# caretaker-switch8.net
KiCad netlist of a schematic drawn in EAGLE
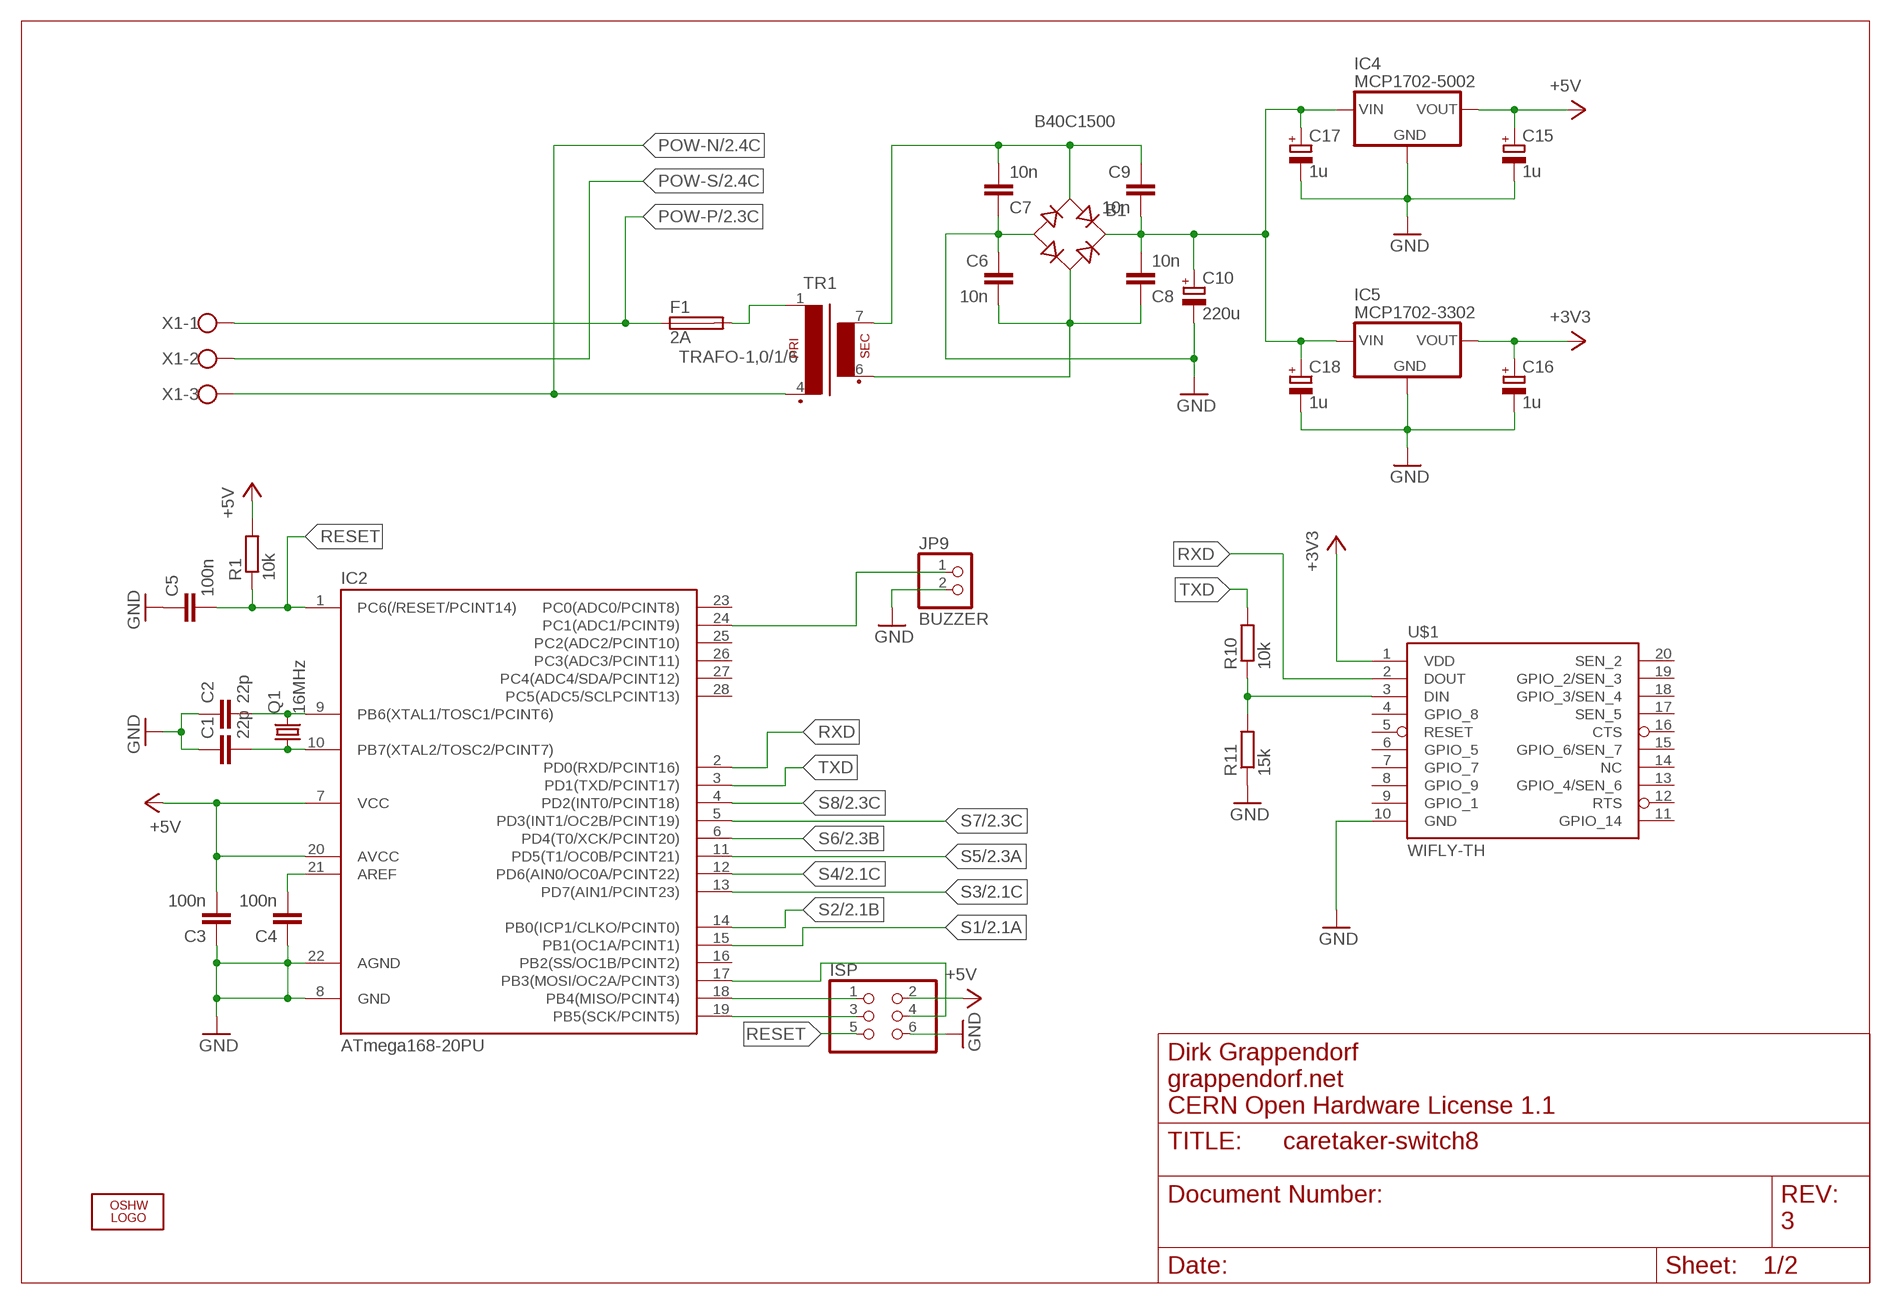
[diagram p0: schematic, sheet 1]
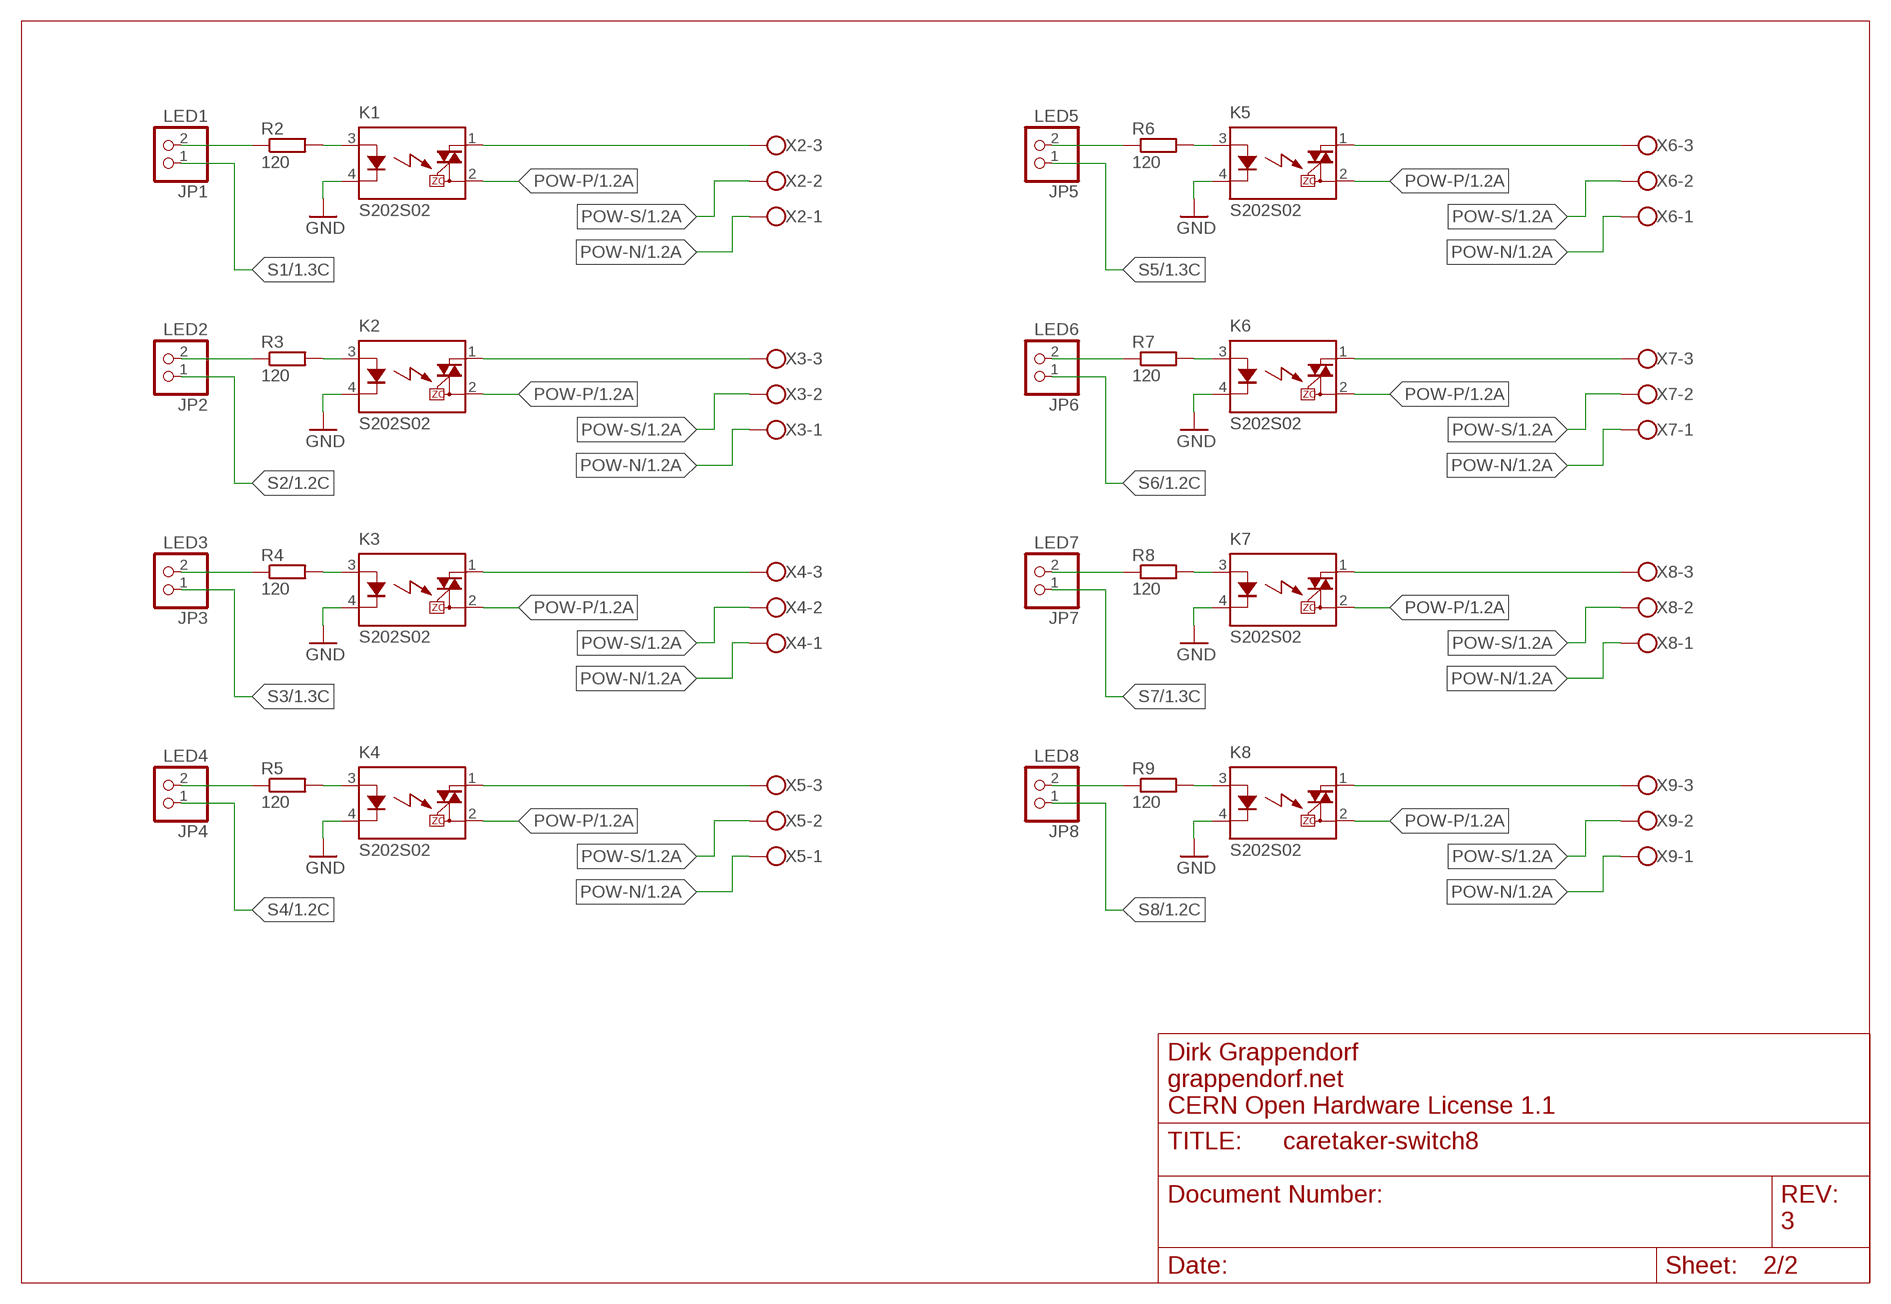
[diagram p1: schematic, sheet 2]

(export (version "E")
  (design (tool "Eeschema 10.0.6"))
  (components
    (comp (ref "JP1")
      (value "LED1")
      (footprint "eagle-import:1X02")
      (libsource (lib "eagle-import") (part "PINHD-1X2"))
    )
    (comp (ref "JP2")
      (value "LED2")
      (footprint "eagle-import:1X02")
      (libsource (lib "eagle-import") (part "PINHD-1X2"))
    )
    (comp (ref "JP3")
      (value "LED3")
      (footprint "eagle-import:1X02")
      (libsource (lib "eagle-import") (part "PINHD-1X2"))
    )
    (comp (ref "JP4")
      (value "LED4")
      (footprint "eagle-import:1X02")
      (libsource (lib "eagle-import") (part "PINHD-1X2"))
    )
    (comp (ref "JP5")
      (value "LED5")
      (footprint "eagle-import:1X02")
      (libsource (lib "eagle-import") (part "PINHD-1X2"))
    )
    (comp (ref "JP6")
      (value "LED6")
      (footprint "eagle-import:1X02")
      (libsource (lib "eagle-import") (part "PINHD-1X2"))
    )
    (comp (ref "JP7")
      (value "LED7")
      (footprint "eagle-import:1X02")
      (libsource (lib "eagle-import") (part "PINHD-1X2"))
    )
    (comp (ref "JP8")
      (value "LED8")
      (footprint "eagle-import:1X02")
      (libsource (lib "eagle-import") (part "PINHD-1X2"))
    )
    (comp (ref "K1")
      (value "S202S02")
      (footprint "eagle-import:S202S02")
      (libsource (lib "eagle-import") (part "S02S022"))
    )
    (comp (ref "K2")
      (value "S202S02")
      (footprint "eagle-import:S202S02")
      (libsource (lib "eagle-import") (part "S02S022"))
    )
    (comp (ref "K3")
      (value "S202S02")
      (footprint "eagle-import:S202S02")
      (libsource (lib "eagle-import") (part "S02S022"))
    )
    (comp (ref "K4")
      (value "S202S02")
      (footprint "eagle-import:S202S02")
      (libsource (lib "eagle-import") (part "S02S022"))
    )
    (comp (ref "K5")
      (value "S202S02")
      (footprint "eagle-import:S202S02")
      (libsource (lib "eagle-import") (part "S02S022"))
    )
    (comp (ref "K6")
      (value "S202S02")
      (footprint "eagle-import:S202S02")
      (libsource (lib "eagle-import") (part "S02S022"))
    )
    (comp (ref "K7")
      (value "S202S02")
      (footprint "eagle-import:S202S02")
      (libsource (lib "eagle-import") (part "S02S022"))
    )
    (comp (ref "K8")
      (value "S202S02")
      (footprint "eagle-import:S202S02")
      (libsource (lib "eagle-import") (part "S02S022"))
    )
    (comp (ref "R2")
      (value "120")
      (footprint "eagle-import:0204_7")
      (libsource (lib "eagle-import") (part "R-EU_0204/7"))
    )
    (comp (ref "R3")
      (value "120")
      (footprint "eagle-import:0204_7")
      (libsource (lib "eagle-import") (part "R-EU_0204/7"))
    )
    (comp (ref "R4")
      (value "120")
      (footprint "eagle-import:0204_7")
      (libsource (lib "eagle-import") (part "R-EU_0204/7"))
    )
    (comp (ref "R5")
      (value "120")
      (footprint "eagle-import:0204_7")
      (libsource (lib "eagle-import") (part "R-EU_0204/7"))
    )
    (comp (ref "R6")
      (value "120")
      (footprint "eagle-import:0204_7")
      (libsource (lib "eagle-import") (part "R-EU_0204/7"))
    )
    (comp (ref "R7")
      (value "120")
      (footprint "eagle-import:0204_7")
      (libsource (lib "eagle-import") (part "R-EU_0204/7"))
    )
    (comp (ref "R8")
      (value "120")
      (footprint "eagle-import:0204_7")
      (libsource (lib "eagle-import") (part "R-EU_0204/7"))
    )
    (comp (ref "R9")
      (value "120")
      (footprint "eagle-import:0204_7")
      (libsource (lib "eagle-import") (part "R-EU_0204/7"))
    )
    (comp (ref "X2")
      (value "W237-103")
      (footprint "eagle-import:W237-103")
      (libsource (lib "eagle-import") (part "W237-103"))
    )
    (comp (ref "X3")
      (value "W237-103")
      (footprint "eagle-import:W237-103")
      (libsource (lib "eagle-import") (part "W237-103"))
    )
    (comp (ref "X4")
      (value "W237-103")
      (footprint "eagle-import:W237-103")
      (libsource (lib "eagle-import") (part "W237-103"))
    )
    (comp (ref "X5")
      (value "W237-103")
      (footprint "eagle-import:W237-103")
      (libsource (lib "eagle-import") (part "W237-103"))
    )
    (comp (ref "X6")
      (value "W237-103")
      (footprint "eagle-import:W237-103")
      (libsource (lib "eagle-import") (part "W237-103"))
    )
    (comp (ref "X7")
      (value "W237-103")
      (footprint "eagle-import:W237-103")
      (libsource (lib "eagle-import") (part "W237-103"))
    )
    (comp (ref "X8")
      (value "W237-103")
      (footprint "eagle-import:W237-103")
      (libsource (lib "eagle-import") (part "W237-103"))
    )
    (comp (ref "X9")
      (value "W237-103")
      (footprint "eagle-import:W237-103")
      (libsource (lib "eagle-import") (part "W237-103"))
    )
    (comp (ref "B1")
      (value "B40C1500")
      (footprint "eagle-import:2KBB")
      (libsource (lib "eagle-import") (part "RECTIFIER-2KBB"))
    )
    (comp (ref "C1")
      (value "22p")
      (footprint "eagle-import:C025-025X050")
      (libsource (lib "eagle-import") (part "C-EU025-025X050"))
    )
    (comp (ref "C2")
      (value "22p")
      (footprint "eagle-import:C025-025X050")
      (libsource (lib "eagle-import") (part "C-EU025-025X050"))
    )
    (comp (ref "C3")
      (value "100n")
      (footprint "eagle-import:C025-024X044")
      (libsource (lib "eagle-import") (part "C-EU025-024X044"))
    )
    (comp (ref "C4")
      (value "100n")
      (footprint "eagle-import:C025-024X044")
      (libsource (lib "eagle-import") (part "C-EU025-024X044"))
    )
    (comp (ref "C5")
      (value "100n")
      (footprint "eagle-import:C025-024X044")
      (libsource (lib "eagle-import") (part "C-EU025-024X044"))
    )
    (comp (ref "C6")
      (value "10n")
      (footprint "eagle-import:C025-024X044")
      (libsource (lib "eagle-import") (part "C-EU025-024X044"))
    )
    (comp (ref "C7")
      (value "10n")
      (footprint "eagle-import:C025-024X044")
      (libsource (lib "eagle-import") (part "C-EU025-024X044"))
    )
    (comp (ref "C8")
      (value "10n")
      (footprint "eagle-import:C025-024X044")
      (libsource (lib "eagle-import") (part "C-EU025-024X044"))
    )
    (comp (ref "C9")
      (value "10n")
      (footprint "eagle-import:C025-024X044")
      (libsource (lib "eagle-import") (part "C-EU025-024X044"))
    )
    (comp (ref "C10")
      (value "220u")
      (footprint "eagle-import:E3,5-8")
      (libsource (lib "eagle-import") (part "CPOL-EUE3.5-8"))
    )
    (comp (ref "C15")
      (value "1u")
      (footprint "eagle-import:E2,5-5")
      (libsource (lib "eagle-import") (part "CPOL-EUE2.5-5"))
    )
    (comp (ref "C16")
      (value "1u")
      (footprint "eagle-import:E2,5-5")
      (libsource (lib "eagle-import") (part "CPOL-EUE2.5-5"))
    )
    (comp (ref "C17")
      (value "1u")
      (footprint "eagle-import:E2,5-5")
      (libsource (lib "eagle-import") (part "CPOL-EUE2.5-5"))
    )
    (comp (ref "C18")
      (value "1u")
      (footprint "eagle-import:E2,5-5")
      (libsource (lib "eagle-import") (part "CPOL-EUE2.5-5"))
    )
    (comp (ref "F1")
      (value "2A")
      (footprint "eagle-import:SH22,5")
      (libsource (lib "eagle-import") (part "SH22,5"))
    )
    (comp (ref "IC2")
      (value "ATmega168-20PU")
      (footprint "eagle-import:DIL28-3")
      (libsource (lib "eagle-import") (part "ATMEGA48/88/168-PU"))
    )
    (comp (ref "IC4")
      (value "MCP1702-5002")
      (footprint "eagle-import:MCP1702")
      (libsource (lib "eagle-import") (part "MCP1702"))
    )
    (comp (ref "IC5")
      (value "MCP1702-3302")
      (footprint "eagle-import:MCP1702")
      (libsource (lib "eagle-import") (part "MCP1702"))
    )
    (comp (ref "ISP")
      (value "PINHD-2X3")
      (footprint "eagle-import:2X03")
      (libsource (lib "eagle-import") (part "PINHD-2X3"))
    )
    (comp (ref "JP9")
      (value "BUZZER")
      (footprint "eagle-import:1X02")
      (libsource (lib "eagle-import") (part "PINHD-1X2"))
    )
    (comp (ref "LOGO1")
      (value "OSHW_LOGO_10MILX0350-NT-BOTTOM")
      (footprint "eagle-import:OSHW_10X350_NOTEXT_BOTTOM")
      (libsource (lib "eagle-import") (part "OSHW_LOGO_10MILX0350-NT-BOTTOM"))
    )
    (comp (ref "Q1")
      (value "16MHz")
      (footprint "eagle-import:HC49U-V")
      (libsource (lib "eagle-import") (part "CRYSTALHC49U-V"))
    )
    (comp (ref "R1")
      (value "10k")
      (footprint "eagle-import:0204_7")
      (libsource (lib "eagle-import") (part "R-EU_0204/7"))
    )
    (comp (ref "R10")
      (value "10k")
      (footprint "eagle-import:0204_7")
      (libsource (lib "eagle-import") (part "R-EU_0204/7"))
    )
    (comp (ref "R11")
      (value "15k")
      (footprint "eagle-import:0204_7")
      (libsource (lib "eagle-import") (part "R-EU_0204/7"))
    )
    (comp (ref "TR1")
      (value "TRAFO-1,0/1/6")
      (footprint "eagle-import:TRAFO-1,0_1_6")
      (libsource (lib "eagle-import") (part "TRAFO-1,0/1/6"))
    )
    (comp (ref "U$1")
      (value "WIFLY-TH")
      (footprint "eagle-import:WIFLY-TH")
      (libsource (lib "eagle-import") (part "WIFLY-TH"))
    )
    (comp (ref "X1")
      (value "W237-103")
      (footprint "eagle-import:W237-103")
      (libsource (lib "eagle-import") (part "W237-103"))
    )
  )
  (nets
    (net (code "1") (name "+3V3") (class "Default")
      (node (ref "C16") (pin "+") (pinfunction "+_+") (pintype "passive"))
      (node (ref "IC5") (pin "VOUT") (pinfunction "OUT_VOUT") (pintype "passive"))
      (node (ref "U$1") (pin "1") (pinfunction "VDD_1") (pintype "power_in"))
    )
    (net (code "2") (name "+5V") (class "Default")
      (node (ref "C15") (pin "+") (pinfunction "+_+") (pintype "passive"))
      (node (ref "C3") (pin "2") (pinfunction "2_2") (pintype "passive"))
      (node (ref "IC2") (pin "20") (pinfunction "AVCC_20") (pintype "passive"))
      (node (ref "IC2") (pin "7") (pinfunction "VCC_7") (pintype "power_in"))
      (node (ref "IC4") (pin "VOUT") (pinfunction "OUT_VOUT") (pintype "passive"))
      (node (ref "ISP") (pin "2") (pinfunction "2_2") (pintype "passive"))
      (node (ref "R1") (pin "2") (pinfunction "2_2") (pintype "passive"))
    )
    (net (code "3") (name "GND") (class "Default")
      (node (ref "B1") (pin "-") (pinfunction "-_-") (pintype "passive"))
      (node (ref "C1") (pin "1") (pinfunction "1_1") (pintype "passive"))
      (node (ref "C10") (pin "-") (pinfunction "-_-") (pintype "passive"))
      (node (ref "C15") (pin "-") (pinfunction "-_-") (pintype "passive"))
      (node (ref "C16") (pin "-") (pinfunction "-_-") (pintype "passive"))
      (node (ref "C17") (pin "-") (pinfunction "-_-") (pintype "passive"))
      (node (ref "C18") (pin "-") (pinfunction "-_-") (pintype "passive"))
      (node (ref "C2") (pin "1") (pinfunction "1_1") (pintype "passive"))
      (node (ref "C3") (pin "1") (pinfunction "1_1") (pintype "passive"))
      (node (ref "C4") (pin "1") (pinfunction "1_1") (pintype "passive"))
      (node (ref "C5") (pin "1") (pinfunction "1_1") (pintype "passive"))
      (node (ref "C6") (pin "1") (pinfunction "1_1") (pintype "passive"))
      (node (ref "C7") (pin "1") (pinfunction "1_1") (pintype "passive"))
      (node (ref "IC2") (pin "22") (pinfunction "AGND_22") (pintype "power_in"))
      (node (ref "IC2") (pin "8") (pinfunction "GND_8") (pintype "power_in"))
      (node (ref "IC4") (pin "GND") (pinfunction "GND_GND") (pintype "input"))
      (node (ref "IC5") (pin "GND") (pinfunction "GND_GND") (pintype "input"))
      (node (ref "ISP") (pin "6") (pinfunction "6_6") (pintype "passive"))
      (node (ref "JP9") (pin "2") (pinfunction "2_2") (pintype "passive"))
      (node (ref "K1") (pin "4") (pinfunction "K_4") (pintype "passive"))
      (node (ref "K2") (pin "4") (pinfunction "K_4") (pintype "passive"))
      (node (ref "K3") (pin "4") (pinfunction "K_4") (pintype "passive"))
      (node (ref "K4") (pin "4") (pinfunction "K_4") (pintype "passive"))
      (node (ref "K5") (pin "4") (pinfunction "K_4") (pintype "passive"))
      (node (ref "K6") (pin "4") (pinfunction "K_4") (pintype "passive"))
      (node (ref "K7") (pin "4") (pinfunction "K_4") (pintype "passive"))
      (node (ref "K8") (pin "4") (pinfunction "K_4") (pintype "passive"))
      (node (ref "R11") (pin "1") (pinfunction "1_1") (pintype "passive"))
      (node (ref "U$1") (pin "10") (pinfunction "GND_10") (pintype "power_in"))
    )
    (net (code "4") (name "Net-(IC2-AREF)") (class "Default")
      (node (ref "C4") (pin "2") (pinfunction "2_2") (pintype "passive"))
      (node (ref "IC2") (pin "21") (pinfunction "AREF_21") (pintype "passive"))
    )
    (net (code "5") (name "Net-(IC2-PB3(MOSI{slash}OC2A{slash}PCINT3))") (class "Default")
      (node (ref "IC2") (pin "17") (pinfunction "PB3(MOSI/OC2A/PCINT3)_17") (pintype "bidirectional"))
      (node (ref "ISP") (pin "4") (pinfunction "4_4") (pintype "passive"))
    )
    (net (code "6") (name "Net-(IC2-PB4(MISO{slash}PCINT4))") (class "Default")
      (node (ref "IC2") (pin "18") (pinfunction "PB4(MISO/PCINT4)_18") (pintype "bidirectional"))
      (node (ref "ISP") (pin "1") (pinfunction "1_1") (pintype "passive"))
    )
    (net (code "7") (name "Net-(IC2-PB5(SCK{slash}PCINT5))") (class "Default")
      (node (ref "IC2") (pin "19") (pinfunction "PB5(SCK/PCINT5)_19") (pintype "bidirectional"))
      (node (ref "ISP") (pin "3") (pinfunction "3_3") (pintype "passive"))
    )
    (net (code "8") (name "Net-(IC2-PB6(XTAL1{slash}TOSC1{slash}PCINT6))") (class "Default")
      (node (ref "C2") (pin "2") (pinfunction "2_2") (pintype "passive"))
      (node (ref "IC2") (pin "9") (pinfunction "PB6(XTAL1/TOSC1/PCINT6)_9") (pintype "bidirectional"))
      (node (ref "Q1") (pin "2") (pinfunction "2_2") (pintype "passive"))
    )
    (net (code "9") (name "Net-(IC2-PB7(XTAL2{slash}TOSC2{slash}PCINT7))") (class "Default")
      (node (ref "C1") (pin "2") (pinfunction "2_2") (pintype "passive"))
      (node (ref "IC2") (pin "10") (pinfunction "PB7(XTAL2/TOSC2/PCINT7)_10") (pintype "bidirectional"))
      (node (ref "Q1") (pin "1") (pinfunction "1_1") (pintype "passive"))
    )
    (net (code "10") (name "Net-(IC2-PC1(ADC1{slash}PCINT9))") (class "Default")
      (node (ref "IC2") (pin "24") (pinfunction "PC1(ADC1/PCINT9)_24") (pintype "bidirectional"))
      (node (ref "JP9") (pin "1") (pinfunction "1_1") (pintype "passive"))
    )
    (net (code "11") (name "Net-(IC4-IN)") (class "Default")
      (node (ref "B1") (pin "+") (pinfunction "+_+") (pintype "passive"))
      (node (ref "C10") (pin "+") (pinfunction "+_+") (pintype "passive"))
      (node (ref "C17") (pin "+") (pinfunction "+_+") (pintype "passive"))
      (node (ref "C18") (pin "+") (pinfunction "+_+") (pintype "passive"))
      (node (ref "C8") (pin "2") (pinfunction "2_2") (pintype "passive"))
      (node (ref "C9") (pin "2") (pinfunction "2_2") (pintype "passive"))
      (node (ref "IC4") (pin "VIN") (pinfunction "IN_VIN") (pintype "input"))
      (node (ref "IC5") (pin "VIN") (pinfunction "IN_VIN") (pintype "input"))
    )
    (net (code "12") (name "Net-(JP1-Pad2)") (class "Default")
      (node (ref "JP1") (pin "2") (pinfunction "2_2") (pintype "passive"))
      (node (ref "R2") (pin "1") (pinfunction "1_1") (pintype "passive"))
    )
    (net (code "13") (name "Net-(JP2-Pad2)") (class "Default")
      (node (ref "JP2") (pin "2") (pinfunction "2_2") (pintype "passive"))
      (node (ref "R3") (pin "1") (pinfunction "1_1") (pintype "passive"))
    )
    (net (code "14") (name "Net-(JP3-Pad2)") (class "Default")
      (node (ref "JP3") (pin "2") (pinfunction "2_2") (pintype "passive"))
      (node (ref "R4") (pin "1") (pinfunction "1_1") (pintype "passive"))
    )
    (net (code "15") (name "Net-(JP4-Pad2)") (class "Default")
      (node (ref "JP4") (pin "2") (pinfunction "2_2") (pintype "passive"))
      (node (ref "R5") (pin "1") (pinfunction "1_1") (pintype "passive"))
    )
    (net (code "16") (name "Net-(JP5-Pad2)") (class "Default")
      (node (ref "JP5") (pin "2") (pinfunction "2_2") (pintype "passive"))
      (node (ref "R6") (pin "1") (pinfunction "1_1") (pintype "passive"))
    )
    (net (code "17") (name "Net-(JP6-Pad2)") (class "Default")
      (node (ref "JP6") (pin "2") (pinfunction "2_2") (pintype "passive"))
      (node (ref "R7") (pin "1") (pinfunction "1_1") (pintype "passive"))
    )
    (net (code "18") (name "Net-(JP7-Pad2)") (class "Default")
      (node (ref "JP7") (pin "2") (pinfunction "2_2") (pintype "passive"))
      (node (ref "R8") (pin "1") (pinfunction "1_1") (pintype "passive"))
    )
    (net (code "19") (name "Net-(JP8-Pad2)") (class "Default")
      (node (ref "JP8") (pin "2") (pinfunction "2_2") (pintype "passive"))
      (node (ref "R9") (pin "1") (pinfunction "1_1") (pintype "passive"))
    )
    (net (code "20") (name "Net-(K1-A)") (class "Default")
      (node (ref "K1") (pin "3") (pinfunction "A_3") (pintype "passive"))
      (node (ref "R2") (pin "2") (pinfunction "2_2") (pintype "passive"))
    )
    (net (code "21") (name "Net-(K1-DS1)") (class "Default")
      (node (ref "K1") (pin "1") (pinfunction "DS1_1") (pintype "passive"))
      (node (ref "X2") (pin "3") (pinfunction "KL_3") (pintype "passive"))
    )
    (net (code "22") (name "Net-(K2-A)") (class "Default")
      (node (ref "K2") (pin "3") (pinfunction "A_3") (pintype "passive"))
      (node (ref "R3") (pin "2") (pinfunction "2_2") (pintype "passive"))
    )
    (net (code "23") (name "Net-(K2-DS1)") (class "Default")
      (node (ref "K2") (pin "1") (pinfunction "DS1_1") (pintype "passive"))
      (node (ref "X3") (pin "3") (pinfunction "KL_3") (pintype "passive"))
    )
    (net (code "24") (name "Net-(K3-A)") (class "Default")
      (node (ref "K3") (pin "3") (pinfunction "A_3") (pintype "passive"))
      (node (ref "R4") (pin "2") (pinfunction "2_2") (pintype "passive"))
    )
    (net (code "25") (name "Net-(K3-DS1)") (class "Default")
      (node (ref "K3") (pin "1") (pinfunction "DS1_1") (pintype "passive"))
      (node (ref "X4") (pin "3") (pinfunction "KL_3") (pintype "passive"))
    )
    (net (code "26") (name "Net-(K4-A)") (class "Default")
      (node (ref "K4") (pin "3") (pinfunction "A_3") (pintype "passive"))
      (node (ref "R5") (pin "2") (pinfunction "2_2") (pintype "passive"))
    )
    (net (code "27") (name "Net-(K4-DS1)") (class "Default")
      (node (ref "K4") (pin "1") (pinfunction "DS1_1") (pintype "passive"))
      (node (ref "X5") (pin "3") (pinfunction "KL_3") (pintype "passive"))
    )
    (net (code "28") (name "Net-(K5-A)") (class "Default")
      (node (ref "K5") (pin "3") (pinfunction "A_3") (pintype "passive"))
      (node (ref "R6") (pin "2") (pinfunction "2_2") (pintype "passive"))
    )
    (net (code "29") (name "Net-(K5-DS1)") (class "Default")
      (node (ref "K5") (pin "1") (pinfunction "DS1_1") (pintype "passive"))
      (node (ref "X6") (pin "3") (pinfunction "KL_3") (pintype "passive"))
    )
    (net (code "30") (name "Net-(K6-A)") (class "Default")
      (node (ref "K6") (pin "3") (pinfunction "A_3") (pintype "passive"))
      (node (ref "R7") (pin "2") (pinfunction "2_2") (pintype "passive"))
    )
    (net (code "31") (name "Net-(K6-DS1)") (class "Default")
      (node (ref "K6") (pin "1") (pinfunction "DS1_1") (pintype "passive"))
      (node (ref "X7") (pin "3") (pinfunction "KL_3") (pintype "passive"))
    )
    (net (code "32") (name "Net-(K7-A)") (class "Default")
      (node (ref "K7") (pin "3") (pinfunction "A_3") (pintype "passive"))
      (node (ref "R8") (pin "2") (pinfunction "2_2") (pintype "passive"))
    )
    (net (code "33") (name "Net-(K7-DS1)") (class "Default")
      (node (ref "K7") (pin "1") (pinfunction "DS1_1") (pintype "passive"))
      (node (ref "X8") (pin "3") (pinfunction "KL_3") (pintype "passive"))
    )
    (net (code "34") (name "Net-(K8-A)") (class "Default")
      (node (ref "K8") (pin "3") (pinfunction "A_3") (pintype "passive"))
      (node (ref "R9") (pin "2") (pinfunction "2_2") (pintype "passive"))
    )
    (net (code "35") (name "Net-(K8-DS1)") (class "Default")
      (node (ref "K8") (pin "1") (pinfunction "DS1_1") (pintype "passive"))
      (node (ref "X9") (pin "3") (pinfunction "KL_3") (pintype "passive"))
    )
    (net (code "36") (name "Net-(TR1-P1)") (class "Default")
      (node (ref "F1") (pin "2") (pinfunction "2_2") (pintype "passive"))
      (node (ref "TR1") (pin "1") (pinfunction "P1_1") (pintype "passive"))
    )
    (net (code "37") (name "Net-(TR1-S3)") (class "Default")
      (node (ref "B1") (pin "AC2") (pinfunction "AC2_AC2") (pintype "passive"))
      (node (ref "C6") (pin "2") (pinfunction "2_2") (pintype "passive"))
      (node (ref "C8") (pin "1") (pinfunction "1_1") (pintype "passive"))
      (node (ref "TR1") (pin "6") (pinfunction "S3_6") (pintype "passive"))
    )
    (net (code "38") (name "Net-(TR1-S4)") (class "Default")
      (node (ref "B1") (pin "AC1") (pinfunction "AC1_AC1") (pintype "passive"))
      (node (ref "C7") (pin "2") (pinfunction "2_2") (pintype "passive"))
      (node (ref "C9") (pin "1") (pinfunction "1_1") (pintype "passive"))
      (node (ref "TR1") (pin "7") (pinfunction "S4_7") (pintype "passive"))
    )
    (net (code "39") (name "Net-(U$1-DIN)") (class "Default")
      (node (ref "R10") (pin "1") (pinfunction "1_1") (pintype "passive"))
      (node (ref "R11") (pin "2") (pinfunction "2_2") (pintype "passive"))
      (node (ref "U$1") (pin "3") (pinfunction "DIN_3") (pintype "input"))
    )
    (net (code "40") (name "POW-N") (class "Default")
      (node (ref "TR1") (pin "4") (pinfunction "P2_4") (pintype "passive"))
      (node (ref "X1") (pin "3") (pinfunction "KL_3") (pintype "passive"))
      (node (ref "X2") (pin "1") (pinfunction "KL_1") (pintype "passive"))
      (node (ref "X3") (pin "1") (pinfunction "KL_1") (pintype "passive"))
      (node (ref "X4") (pin "1") (pinfunction "KL_1") (pintype "passive"))
      (node (ref "X5") (pin "1") (pinfunction "KL_1") (pintype "passive"))
      (node (ref "X6") (pin "1") (pinfunction "KL_1") (pintype "passive"))
      (node (ref "X7") (pin "1") (pinfunction "KL_1") (pintype "passive"))
      (node (ref "X8") (pin "1") (pinfunction "KL_1") (pintype "passive"))
      (node (ref "X9") (pin "1") (pinfunction "KL_1") (pintype "passive"))
    )
    (net (code "41") (name "POW-P") (class "Default")
      (node (ref "F1") (pin "1") (pinfunction "1_1") (pintype "passive"))
      (node (ref "K1") (pin "2") (pinfunction "DS2_2") (pintype "passive"))
      (node (ref "K2") (pin "2") (pinfunction "DS2_2") (pintype "passive"))
      (node (ref "K3") (pin "2") (pinfunction "DS2_2") (pintype "passive"))
      (node (ref "K4") (pin "2") (pinfunction "DS2_2") (pintype "passive"))
      (node (ref "K5") (pin "2") (pinfunction "DS2_2") (pintype "passive"))
      (node (ref "K6") (pin "2") (pinfunction "DS2_2") (pintype "passive"))
      (node (ref "K7") (pin "2") (pinfunction "DS2_2") (pintype "passive"))
      (node (ref "K8") (pin "2") (pinfunction "DS2_2") (pintype "passive"))
      (node (ref "X1") (pin "1") (pinfunction "KL_1") (pintype "passive"))
    )
    (net (code "42") (name "POW-S") (class "Default")
      (node (ref "X1") (pin "2") (pinfunction "KL_2") (pintype "passive"))
      (node (ref "X2") (pin "2") (pinfunction "KL_2") (pintype "passive"))
      (node (ref "X3") (pin "2") (pinfunction "KL_2") (pintype "passive"))
      (node (ref "X4") (pin "2") (pinfunction "KL_2") (pintype "passive"))
      (node (ref "X5") (pin "2") (pinfunction "KL_2") (pintype "passive"))
      (node (ref "X6") (pin "2") (pinfunction "KL_2") (pintype "passive"))
      (node (ref "X7") (pin "2") (pinfunction "KL_2") (pintype "passive"))
      (node (ref "X8") (pin "2") (pinfunction "KL_2") (pintype "passive"))
      (node (ref "X9") (pin "2") (pinfunction "KL_2") (pintype "passive"))
    )
    (net (code "43") (name "RESET") (class "Default")
      (node (ref "C5") (pin "2") (pinfunction "2_2") (pintype "passive"))
      (node (ref "IC2") (pin "1") (pinfunction "PC6(/RESET/PCINT14)_1") (pintype "bidirectional"))
      (node (ref "ISP") (pin "5") (pinfunction "5_5") (pintype "passive"))
      (node (ref "R1") (pin "1") (pinfunction "1_1") (pintype "passive"))
    )
    (net (code "44") (name "RXD") (class "Default")
      (node (ref "IC2") (pin "2") (pinfunction "PD0(RXD/PCINT16)_2") (pintype "bidirectional"))
      (node (ref "U$1") (pin "2") (pinfunction "DOUT_2") (pintype "output"))
    )
    (net (code "45") (name "S1") (class "Default")
      (node (ref "IC2") (pin "15") (pinfunction "PB1(OC1A/PCINT1)_15") (pintype "bidirectional"))
      (node (ref "JP1") (pin "1") (pinfunction "1_1") (pintype "passive"))
    )
    (net (code "46") (name "S2") (class "Default")
      (node (ref "IC2") (pin "14") (pinfunction "PB0(ICP1/CLKO/PCINT0)_14") (pintype "bidirectional"))
      (node (ref "JP2") (pin "1") (pinfunction "1_1") (pintype "passive"))
    )
    (net (code "47") (name "S3") (class "Default")
      (node (ref "IC2") (pin "13") (pinfunction "PD7(AIN1/PCINT23)_13") (pintype "bidirectional"))
      (node (ref "JP3") (pin "1") (pinfunction "1_1") (pintype "passive"))
    )
    (net (code "48") (name "S4") (class "Default")
      (node (ref "IC2") (pin "12") (pinfunction "PD6(AIN0/OC0A/PCINT22)_12") (pintype "bidirectional"))
      (node (ref "JP4") (pin "1") (pinfunction "1_1") (pintype "passive"))
    )
    (net (code "49") (name "S5") (class "Default")
      (node (ref "IC2") (pin "11") (pinfunction "PD5(T1/OC0B/PCINT21)_11") (pintype "bidirectional"))
      (node (ref "JP5") (pin "1") (pinfunction "1_1") (pintype "passive"))
    )
    (net (code "50") (name "S6") (class "Default")
      (node (ref "IC2") (pin "6") (pinfunction "PD4(T0/XCK/PCINT20)_6") (pintype "bidirectional"))
      (node (ref "JP6") (pin "1") (pinfunction "1_1") (pintype "passive"))
    )
    (net (code "51") (name "S7") (class "Default")
      (node (ref "IC2") (pin "5") (pinfunction "PD3(INT1/OC2B/PCINT19)_5") (pintype "bidirectional"))
      (node (ref "JP7") (pin "1") (pinfunction "1_1") (pintype "passive"))
    )
    (net (code "52") (name "S8") (class "Default")
      (node (ref "IC2") (pin "4") (pinfunction "PD2(INT0/PCINT18)_4") (pintype "bidirectional"))
      (node (ref "JP8") (pin "1") (pinfunction "1_1") (pintype "passive"))
    )
    (net (code "53") (name "TXD") (class "Default")
      (node (ref "IC2") (pin "3") (pinfunction "PD1(TXD/PCINT17)_3") (pintype "bidirectional"))
      (node (ref "R10") (pin "2") (pinfunction "2_2") (pintype "passive"))
    )
    (net (code "54") (name "unconnected-(IC2-PB2(SS{slash}OC1B{slash}PCINT2)-Pad16)") (class "Default")
      (node (ref "IC2") (pin "16") (pinfunction "PB2(SS/OC1B/PCINT2)_16") (pintype "bidirectional"))
    )
    (net (code "55") (name "unconnected-(IC2-PC0(ADC0{slash}PCINT8)-Pad23)") (class "Default")
      (node (ref "IC2") (pin "23") (pinfunction "PC0(ADC0/PCINT8)_23") (pintype "bidirectional"))
    )
    (net (code "56") (name "unconnected-(IC2-PC2(ADC2{slash}PCINT10)-Pad25)") (class "Default")
      (node (ref "IC2") (pin "25") (pinfunction "PC2(ADC2/PCINT10)_25") (pintype "bidirectional"))
    )
    (net (code "57") (name "unconnected-(IC2-PC3(ADC3{slash}PCINT11)-Pad26)") (class "Default")
      (node (ref "IC2") (pin "26") (pinfunction "PC3(ADC3/PCINT11)_26") (pintype "bidirectional"))
    )
    (net (code "58") (name "unconnected-(IC2-PC4(ADC4{slash}SDA{slash}PCINT12)-Pad27)") (class "Default")
      (node (ref "IC2") (pin "27") (pinfunction "PC4(ADC4/SDA/PCINT12)_27") (pintype "bidirectional"))
    )
    (net (code "59") (name "unconnected-(IC2-PC5(ADC5{slash}SCLPCINT13)-Pad28)") (class "Default")
      (node (ref "IC2") (pin "28") (pinfunction "PC5(ADC5/SCLPCINT13)_28") (pintype "bidirectional"))
    )
    (net (code "60") (name "unconnected-(U$1-CTS-Pad16)") (class "Default")
      (node (ref "U$1") (pin "16") (pinfunction "CTS_16") (pintype "input"))
    )
    (net (code "61") (name "unconnected-(U$1-GPIO_1-Pad9)") (class "Default")
      (node (ref "U$1") (pin "9") (pinfunction "GPIO_1_9") (pintype "bidirectional"))
    )
    (net (code "62") (name "unconnected-(U$1-GPIO_2{slash}SEN_3-Pad19)") (class "Default")
      (node (ref "U$1") (pin "19") (pinfunction "GPIO_2/SEN_3_19") (pintype "bidirectional"))
    )
    (net (code "63") (name "unconnected-(U$1-GPIO_3{slash}SEN_4-Pad18)") (class "Default")
      (node (ref "U$1") (pin "18") (pinfunction "GPIO_3/SEN_4_18") (pintype "bidirectional"))
    )
    (net (code "64") (name "unconnected-(U$1-GPIO_4{slash}SEN_6-Pad13)") (class "Default")
      (node (ref "U$1") (pin "13") (pinfunction "GPIO_4/SEN_6_13") (pintype "bidirectional"))
    )
    (net (code "65") (name "unconnected-(U$1-GPIO_5-Pad6)") (class "Default")
      (node (ref "U$1") (pin "6") (pinfunction "GPIO_5_6") (pintype "bidirectional"))
    )
    (net (code "66") (name "unconnected-(U$1-GPIO_6{slash}SEN_7-Pad15)") (class "Default")
      (node (ref "U$1") (pin "15") (pinfunction "GPIO_6/SEN_7_15") (pintype "bidirectional"))
    )
    (net (code "67") (name "unconnected-(U$1-GPIO_7-Pad7)") (class "Default")
      (node (ref "U$1") (pin "7") (pinfunction "GPIO_7_7") (pintype "bidirectional"))
    )
    (net (code "68") (name "unconnected-(U$1-GPIO_8-Pad4)") (class "Default")
      (node (ref "U$1") (pin "4") (pinfunction "GPIO_8_4") (pintype "bidirectional"))
    )
    (net (code "69") (name "unconnected-(U$1-GPIO_9-Pad8)") (class "Default")
      (node (ref "U$1") (pin "8") (pinfunction "GPIO_9_8") (pintype "bidirectional"))
    )
    (net (code "70") (name "unconnected-(U$1-GPIO_14-Pad11)") (class "Default")
      (node (ref "U$1") (pin "11") (pinfunction "GPIO_14_11") (pintype "bidirectional"))
    )
    (net (code "71") (name "unconnected-(U$1-NC-Pad14)") (class "Default")
      (node (ref "U$1") (pin "14") (pinfunction "NC_14") (pintype "bidirectional"))
    )
    (net (code "72") (name "unconnected-(U$1-RESET-Pad5)") (class "Default")
      (node (ref "U$1") (pin "5") (pinfunction "RESET_5") (pintype "input"))
    )
    (net (code "73") (name "unconnected-(U$1-RTS-Pad12)") (class "Default")
      (node (ref "U$1") (pin "12") (pinfunction "RTS_12") (pintype "output"))
    )
    (net (code "74") (name "unconnected-(U$1-SEN_2-Pad20)") (class "Default")
      (node (ref "U$1") (pin "20") (pinfunction "SEN_2_20") (pintype "bidirectional"))
    )
    (net (code "75") (name "unconnected-(U$1-SEN_5-Pad17)") (class "Default")
      (node (ref "U$1") (pin "17") (pinfunction "SEN_5_17") (pintype "bidirectional"))
    )
  )
)
